# 11_Power_Input_and_Regualtor.net
KiCad netlist of a schematic drawn in Altium Designer
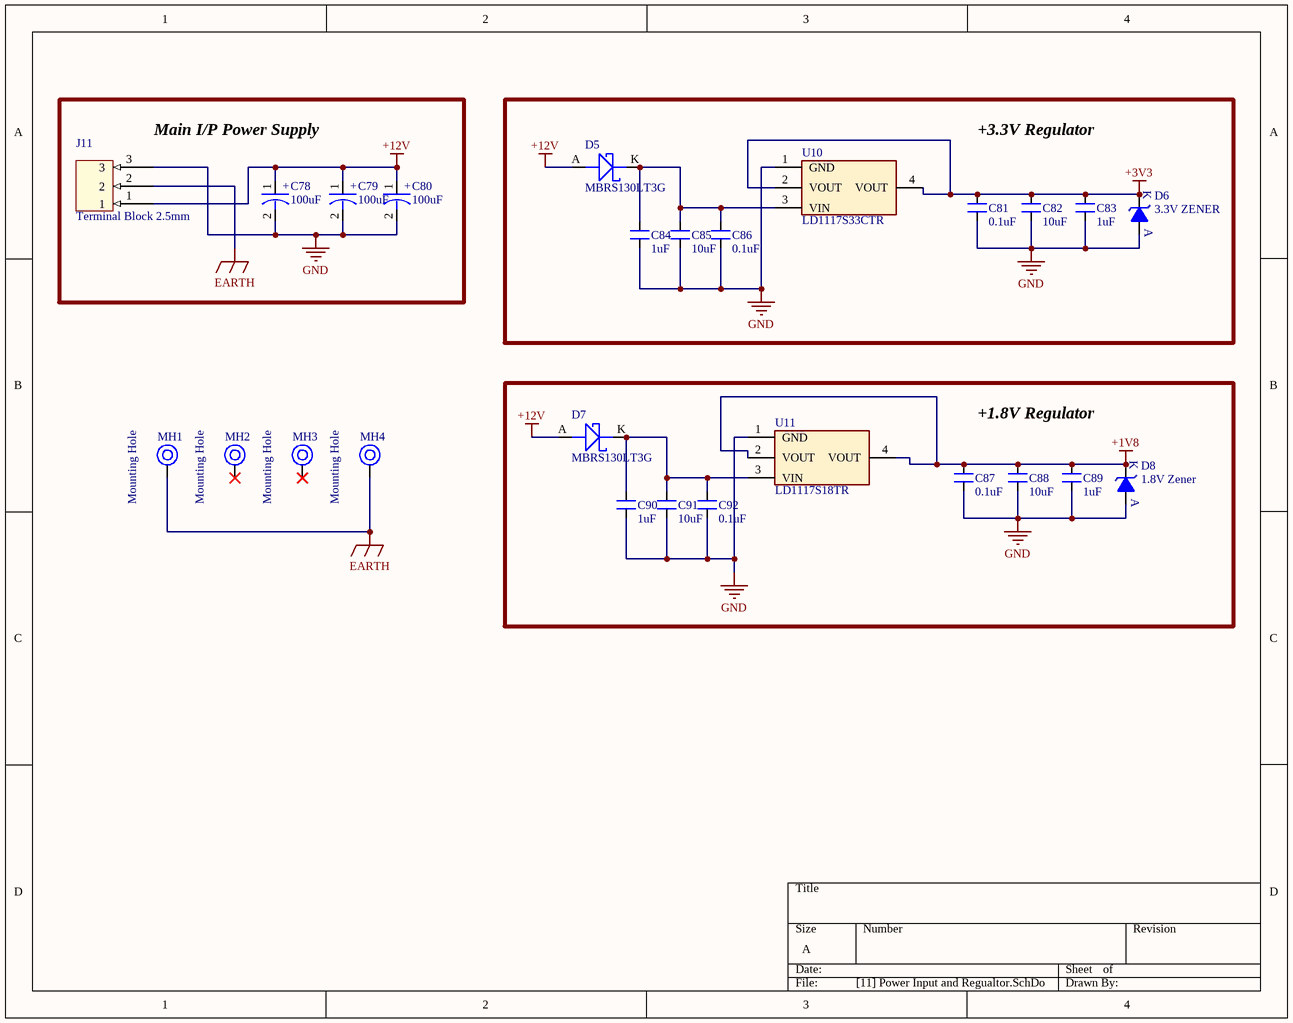
[diagram p0: [11] Power Input and Regualtor.SchDoc]

(export (version "E")
  (design (tool "Eeschema 10.0.6"))
  (components
    (comp (ref "C78")
      (value "100uF")
      (footprint "ACAP_P305_D393_H393_RAD")
      (description "100µF 50V Aluminum Polymer Capacitor Radial, Can - SMD 28mOhm 4000 Hrs @ 125°C")
      (fields
        (field (name "MANUFACTURER") "Nichicon")
        (field (name "MANUFACTURER PART NUMBER") "GYA1H101MCQ1GS")
      )
      (libsource (lib "ESTEEMPCBLIB") (part "CAP-P_100uF-50V-20%-RAD"))
    )
    (comp (ref "C79")
      (value "100uF")
      (footprint "ACAP_P305_D393_H393_RAD")
      (description "100µF 50V Aluminum Polymer Capacitor Radial, Can - SMD 28mOhm 4000 Hrs @ 125°C")
      (fields
        (field (name "MANUFACTURER") "Nichicon")
        (field (name "MANUFACTURER PART NUMBER") "GYA1H101MCQ1GS")
      )
      (libsource (lib "ESTEEMPCBLIB") (part "CAP-P_100uF-50V-20%-RAD"))
    )
    (comp (ref "C80")
      (value "100uF")
      (footprint "ACAP_P305_D393_H393_RAD")
      (description "100µF 50V Aluminum Polymer Capacitor Radial, Can - SMD 28mOhm 4000 Hrs @ 125°C")
      (fields
        (field (name "MANUFACTURER") "Nichicon")
        (field (name "MANUFACTURER PART NUMBER") "GYA1H101MCQ1GS")
      )
      (libsource (lib "ESTEEMPCBLIB") (part "CAP-P_100uF-50V-20%-RAD"))
    )
    (comp (ref "C81")
      (value "0.1uF")
      (footprint "CAP_0805")
      (description "0.1µF ±10% 50V Ceramic Capacitor X7R 0805 (2012 Metric)")
      (fields
        (field (name "MANUFACTURER") "Samsung")
        (field (name "MANUFACTURER PART NUMBER") "CL21B104KBCNNNC")
      )
      (libsource (lib "ESTEEMPCBLIB") (part "CAP_0.1uF-50V-10%-0805"))
    )
    (comp (ref "C82")
      (value "10uF")
      (footprint "CAP_1206")
      (description "10µF ±10% 50V Ceramic Capacitor X7R 1206 (3216 Metric)")
      (fields
        (field (name "MANUFACTURER") "KEMET")
        (field (name "MANUFACTURER PART NUMBER") "CL31B106KBHNNNE")
      )
      (libsource (lib "ESTEEMPCBLIB") (part "CAP_10uF-50V-10%-1206"))
    )
    (comp (ref "C83")
      (value "1uF")
      (footprint "CAP_0805")
      (description "1µF ±5% 50V Ceramic Capacitor X7R 0805 (2012 Metric)")
      (fields
        (field (name "MANUFACTURER") "Samsung")
        (field (name "MANUFACTURER PART NUMBER") "CC0805JKX7R9BB105")
      )
      (libsource (lib "ESTEEMPCBLIB") (part "CAP_1uF-50V-5%-0805"))
    )
    (comp (ref "C84")
      (value "1uF")
      (footprint "CAP_0805")
      (description "1µF ±5% 50V Ceramic Capacitor X7R 0805 (2012 Metric)")
      (fields
        (field (name "MANUFACTURER") "Samsung")
        (field (name "MANUFACTURER PART NUMBER") "CC0805JKX7R9BB105")
      )
      (libsource (lib "ESTEEMPCBLIB") (part "CAP_1uF-50V-5%-0805"))
    )
    (comp (ref "C85")
      (value "10uF")
      (footprint "CAP_1206")
      (description "10µF ±10% 50V Ceramic Capacitor X7R 1206 (3216 Metric)")
      (fields
        (field (name "MANUFACTURER") "KEMET")
        (field (name "MANUFACTURER PART NUMBER") "CL31B106KBHNNNE")
      )
      (libsource (lib "ESTEEMPCBLIB") (part "CAP_10uF-50V-10%-1206"))
    )
    (comp (ref "C86")
      (value "0.1uF")
      (footprint "CAP_0805")
      (description "0.1µF ±10% 50V Ceramic Capacitor X7R 0805 (2012 Metric)")
      (fields
        (field (name "MANUFACTURER") "Samsung")
        (field (name "MANUFACTURER PART NUMBER") "CL21B104KBCNNNC")
      )
      (libsource (lib "ESTEEMPCBLIB") (part "CAP_0.1uF-50V-10%-0805"))
    )
    (comp (ref "C87")
      (value "0.1uF")
      (footprint "CAP_0805")
      (description "0.1µF ±10% 50V Ceramic Capacitor X7R 0805 (2012 Metric)")
      (fields
        (field (name "MANUFACTURER") "Samsung")
        (field (name "MANUFACTURER PART NUMBER") "CL21B104KBCNNNC")
      )
      (libsource (lib "ESTEEMPCBLIB") (part "CAP_0.1uF-50V-10%-0805"))
    )
    (comp (ref "C88")
      (value "10uF")
      (footprint "CAP_1206")
      (description "10µF ±10% 50V Ceramic Capacitor X7R 1206 (3216 Metric)")
      (fields
        (field (name "MANUFACTURER") "KEMET")
        (field (name "MANUFACTURER PART NUMBER") "CL31B106KBHNNNE")
      )
      (libsource (lib "ESTEEMPCBLIB") (part "CAP_10uF-50V-10%-1206"))
    )
    (comp (ref "C89")
      (value "1uF")
      (footprint "CAP_0805")
      (description "1µF ±5% 50V Ceramic Capacitor X7R 0805 (2012 Metric)")
      (fields
        (field (name "MANUFACTURER") "Samsung")
        (field (name "MANUFACTURER PART NUMBER") "CC0805JKX7R9BB105")
      )
      (libsource (lib "ESTEEMPCBLIB") (part "CAP_1uF-50V-5%-0805"))
    )
    (comp (ref "C90")
      (value "1uF")
      (footprint "CAP_0805")
      (description "1µF ±5% 50V Ceramic Capacitor X7R 0805 (2012 Metric)")
      (fields
        (field (name "MANUFACTURER") "Samsung")
        (field (name "MANUFACTURER PART NUMBER") "CC0805JKX7R9BB105")
      )
      (libsource (lib "ESTEEMPCBLIB") (part "CAP_1uF-50V-5%-0805"))
    )
    (comp (ref "C91")
      (value "10uF")
      (footprint "CAP_1206")
      (description "10µF ±10% 50V Ceramic Capacitor X7R 1206 (3216 Metric)")
      (fields
        (field (name "MANUFACTURER") "KEMET")
        (field (name "MANUFACTURER PART NUMBER") "CL31B106KBHNNNE")
      )
      (libsource (lib "ESTEEMPCBLIB") (part "CAP_10uF-50V-10%-1206"))
    )
    (comp (ref "C92")
      (value "0.1uF")
      (footprint "CAP_0805")
      (description "0.1µF ±10% 50V Ceramic Capacitor X7R 0805 (2012 Metric)")
      (fields
        (field (name "MANUFACTURER") "Samsung")
        (field (name "MANUFACTURER PART NUMBER") "CL21B104KBCNNNC")
      )
      (libsource (lib "ESTEEMPCBLIB") (part "CAP_0.1uF-50V-10%-0805"))
    )
    (comp (ref "D5")
      (value "MBRS130LT3G")
      (footprint "DIO_SMB_DO-214AA")
      (description "Diode Schottky 30V 2A Surface Mount SMB")
      (fields (field (name "MANUFACTURER") "ON Semiconductor"))
      (libsource (lib "ESTEEMPCBLIB") (part "DIO-S_445mV-30V-2A-SMB"))
    )
    (comp (ref "D6")
      (value "3.3V ZENER")
      (footprint "DIO_SOD80C")
      (description "Zener Diode 3.3V 500mW ±5% Surface Mount LLDS; MiniMelf")
      (fields
        (field (name "MANUFACTURER") "Vishay Semiconductors")
        (field (name "MANUFACTURER PART NUMBER") "BZV55-C3V3,135")
      )
      (libsource (lib "ESTEEMPCBLIB") (part "DIO-Z_3.3V-500mW-SOD-80"))
    )
    (comp (ref "D7")
      (value "MBRS130LT3G")
      (footprint "DIO_SMB_DO-214AA")
      (description "Diode Schottky 30V 2A Surface Mount SMB")
      (fields (field (name "MANUFACTURER") "ON Semiconductor"))
      (libsource (lib "ESTEEMPCBLIB") (part "DIO-S_445mV-30V-2A-SMB"))
    )
    (comp (ref "D8")
      (value "1.8V Zener")
      (footprint "DIO_DO-213AB_SMD")
      (description "Zener Diode 1.8V 500mW ±5% Surface Mount DO-213AA")
      (libsource (lib "ESTEEMPCBLIB") (part "DIO-Z_1.8V-500mW-DO213AA"))
    )
    (comp (ref "J11")
      (value "Terminal Block 2.5mm")
      (footprint "CON3_100_TB_TH_ST")
      (description "3 Pins, 1 Row 2.54mm Pitch, straight Connector, male")
      (fields
        (field (name "MANUFACTURER PART NUMBER") "1725669")
        (field (name "MANUFACTURER") "Phoenix Contact")
      )
      (libsource (lib "ESTEEMPCBLIB") (part "CON-TB_3X1-100-ST-TH"))
    )
    (comp (ref "MH1")
      (value "Mounting Hole")
      (footprint "MOUNTING")
      (fields (field (name "MANUFACTURER PART NUMBER") "NA"))
      (libsource (lib "ESTEEMPCBLIB") (part "MH_3.5H_6D"))
    )
    (comp (ref "MH2")
      (value "Mounting Hole")
      (footprint "MOUNTING")
      (fields (field (name "MANUFACTURER PART NUMBER") "NA"))
      (libsource (lib "ESTEEMPCBLIB") (part "MH_3.5H_6D"))
    )
    (comp (ref "MH3")
      (value "Mounting Hole")
      (footprint "MOUNTING")
      (fields (field (name "MANUFACTURER PART NUMBER") "NA"))
      (libsource (lib "ESTEEMPCBLIB") (part "MH_3.5H_6D"))
    )
    (comp (ref "MH4")
      (value "Mounting Hole")
      (footprint "MOUNTING")
      (fields (field (name "MANUFACTURER PART NUMBER") "NA"))
      (libsource (lib "ESTEEMPCBLIB") (part "MH_3.5H_6D"))
    )
    (comp (ref "U10")
      (value "LD1117S33CTR")
      (footprint "SOT223_3")
      (description "Linear Voltage Regulator IC 1 Output 800mA SOT-223")
      (fields (field (name "MANUFACTURER") "STMicroelectronics"))
      (libsource (lib "ESTEEMPCBLIB") (part "REG_15V-3.3V-0.9A-12W-SOT223"))
    )
    (comp (ref "U11")
      (value "LD1117S18TR")
      (footprint "SOT223_3")
      (description "LDO Voltage Regulators 1.8V 0.8A Positive")
      (fields (field (name "MANUFACTURER") "STMicroelectronics"))
      (libsource (lib "ESTEEMPCBLIB") (part "REG_15V-1.8V-0.8A-1.4W-SOT223"))
    )
  )
  (nets
    (net (code "1") (name "+1V8") (class "Default")
      (node (ref "C87") (pin "2") (pinfunction "2_2") (pintype "passive"))
      (node (ref "C88") (pin "1") (pinfunction "1_1") (pintype "passive"))
      (node (ref "C89") (pin "2") (pinfunction "2_2") (pintype "passive"))
      (node (ref "D8") (pin "K") (pinfunction "K_K") (pintype "passive"))
      (node (ref "U11") (pin "2") (pinfunction "VOUT_2") (pintype "passive"))
      (node (ref "U11") (pin "4") (pinfunction "VOUT_4") (pintype "passive"))
    )
    (net (code "2") (name "+3V3") (class "Default")
      (node (ref "C81") (pin "2") (pinfunction "2_2") (pintype "passive"))
      (node (ref "C82") (pin "1") (pinfunction "1_1") (pintype "passive"))
      (node (ref "C83") (pin "2") (pinfunction "2_2") (pintype "passive"))
      (node (ref "D6") (pin "K") (pinfunction "K_K") (pintype "passive"))
      (node (ref "U10") (pin "2") (pinfunction "VOUT_2") (pintype "passive"))
      (node (ref "U10") (pin "4") (pinfunction "VOUT_4") (pintype "passive"))
    )
    (net (code "3") (name "+12V") (class "Default")
      (node (ref "C78") (pin "1") (pinfunction "1_1") (pintype "passive"))
      (node (ref "C79") (pin "1") (pinfunction "1_1") (pintype "passive"))
      (node (ref "C80") (pin "1") (pinfunction "1_1") (pintype "passive"))
      (node (ref "D5") (pin "A") (pinfunction "A_A") (pintype "passive"))
      (node (ref "D7") (pin "A") (pinfunction "A_A") (pintype "passive"))
      (node (ref "J11") (pin "1") (pinfunction "1_1") (pintype "input"))
    )
    (net (code "4") (name "EARTH") (class "Default")
      (node (ref "J11") (pin "2") (pinfunction "2_2") (pintype "input"))
      (node (ref "MH1") (pin "1") (pinfunction "1_1") (pintype "passive"))
      (node (ref "MH4") (pin "1") (pinfunction "1_1") (pintype "passive"))
    )
    (net (code "5") (name "GND") (class "Default")
      (node (ref "C78") (pin "2") (pinfunction "2_2") (pintype "passive"))
      (node (ref "C79") (pin "2") (pinfunction "2_2") (pintype "passive"))
      (node (ref "C80") (pin "2") (pinfunction "2_2") (pintype "passive"))
      (node (ref "C81") (pin "1") (pinfunction "1_1") (pintype "passive"))
      (node (ref "C82") (pin "2") (pinfunction "2_2") (pintype "passive"))
      (node (ref "C83") (pin "1") (pinfunction "1_1") (pintype "passive"))
      (node (ref "C84") (pin "1") (pinfunction "1_1") (pintype "passive"))
      (node (ref "C85") (pin "2") (pinfunction "2_2") (pintype "passive"))
      (node (ref "C86") (pin "1") (pinfunction "1_1") (pintype "passive"))
      (node (ref "C87") (pin "1") (pinfunction "1_1") (pintype "passive"))
      (node (ref "C88") (pin "2") (pinfunction "2_2") (pintype "passive"))
      (node (ref "C89") (pin "1") (pinfunction "1_1") (pintype "passive"))
      (node (ref "C90") (pin "1") (pinfunction "1_1") (pintype "passive"))
      (node (ref "C91") (pin "2") (pinfunction "2_2") (pintype "passive"))
      (node (ref "C92") (pin "1") (pinfunction "1_1") (pintype "passive"))
      (node (ref "D6") (pin "A") (pinfunction "A_A") (pintype "passive"))
      (node (ref "D8") (pin "A") (pinfunction "A_A") (pintype "passive"))
      (node (ref "J11") (pin "3") (pinfunction "3_3") (pintype "input"))
      (node (ref "U10") (pin "1") (pinfunction "GND_1") (pintype "passive"))
      (node (ref "U11") (pin "1") (pinfunction "GND_1") (pintype "passive"))
    )
    (net (code "6") (name "Net-(U10-VIN)") (class "Default")
      (node (ref "C84") (pin "2") (pinfunction "2_2") (pintype "passive"))
      (node (ref "C85") (pin "1") (pinfunction "1_1") (pintype "passive"))
      (node (ref "C86") (pin "2") (pinfunction "2_2") (pintype "passive"))
      (node (ref "D5") (pin "K") (pinfunction "K_K") (pintype "passive"))
      (node (ref "U10") (pin "3") (pinfunction "VIN_3") (pintype "passive"))
    )
    (net (code "7") (name "Net-(U11-VIN)") (class "Default")
      (node (ref "C90") (pin "2") (pinfunction "2_2") (pintype "passive"))
      (node (ref "C91") (pin "1") (pinfunction "1_1") (pintype "passive"))
      (node (ref "C92") (pin "2") (pinfunction "2_2") (pintype "passive"))
      (node (ref "D7") (pin "K") (pinfunction "K_K") (pintype "passive"))
      (node (ref "U11") (pin "3") (pinfunction "VIN_3") (pintype "passive"))
    )
    (net (code "8") (name "unconnected-(MH2-Pad1)") (class "Default")
      (node (ref "MH2") (pin "1") (pinfunction "1_1") (pintype "passive+no_connect"))
    )
    (net (code "9") (name "unconnected-(MH3-Pad1)") (class "Default")
      (node (ref "MH3") (pin "1") (pinfunction "1_1") (pintype "passive+no_connect"))
    )
  )
)
